# irs-takachi.net
KiCad netlist of a schematic drawn in EAGLE
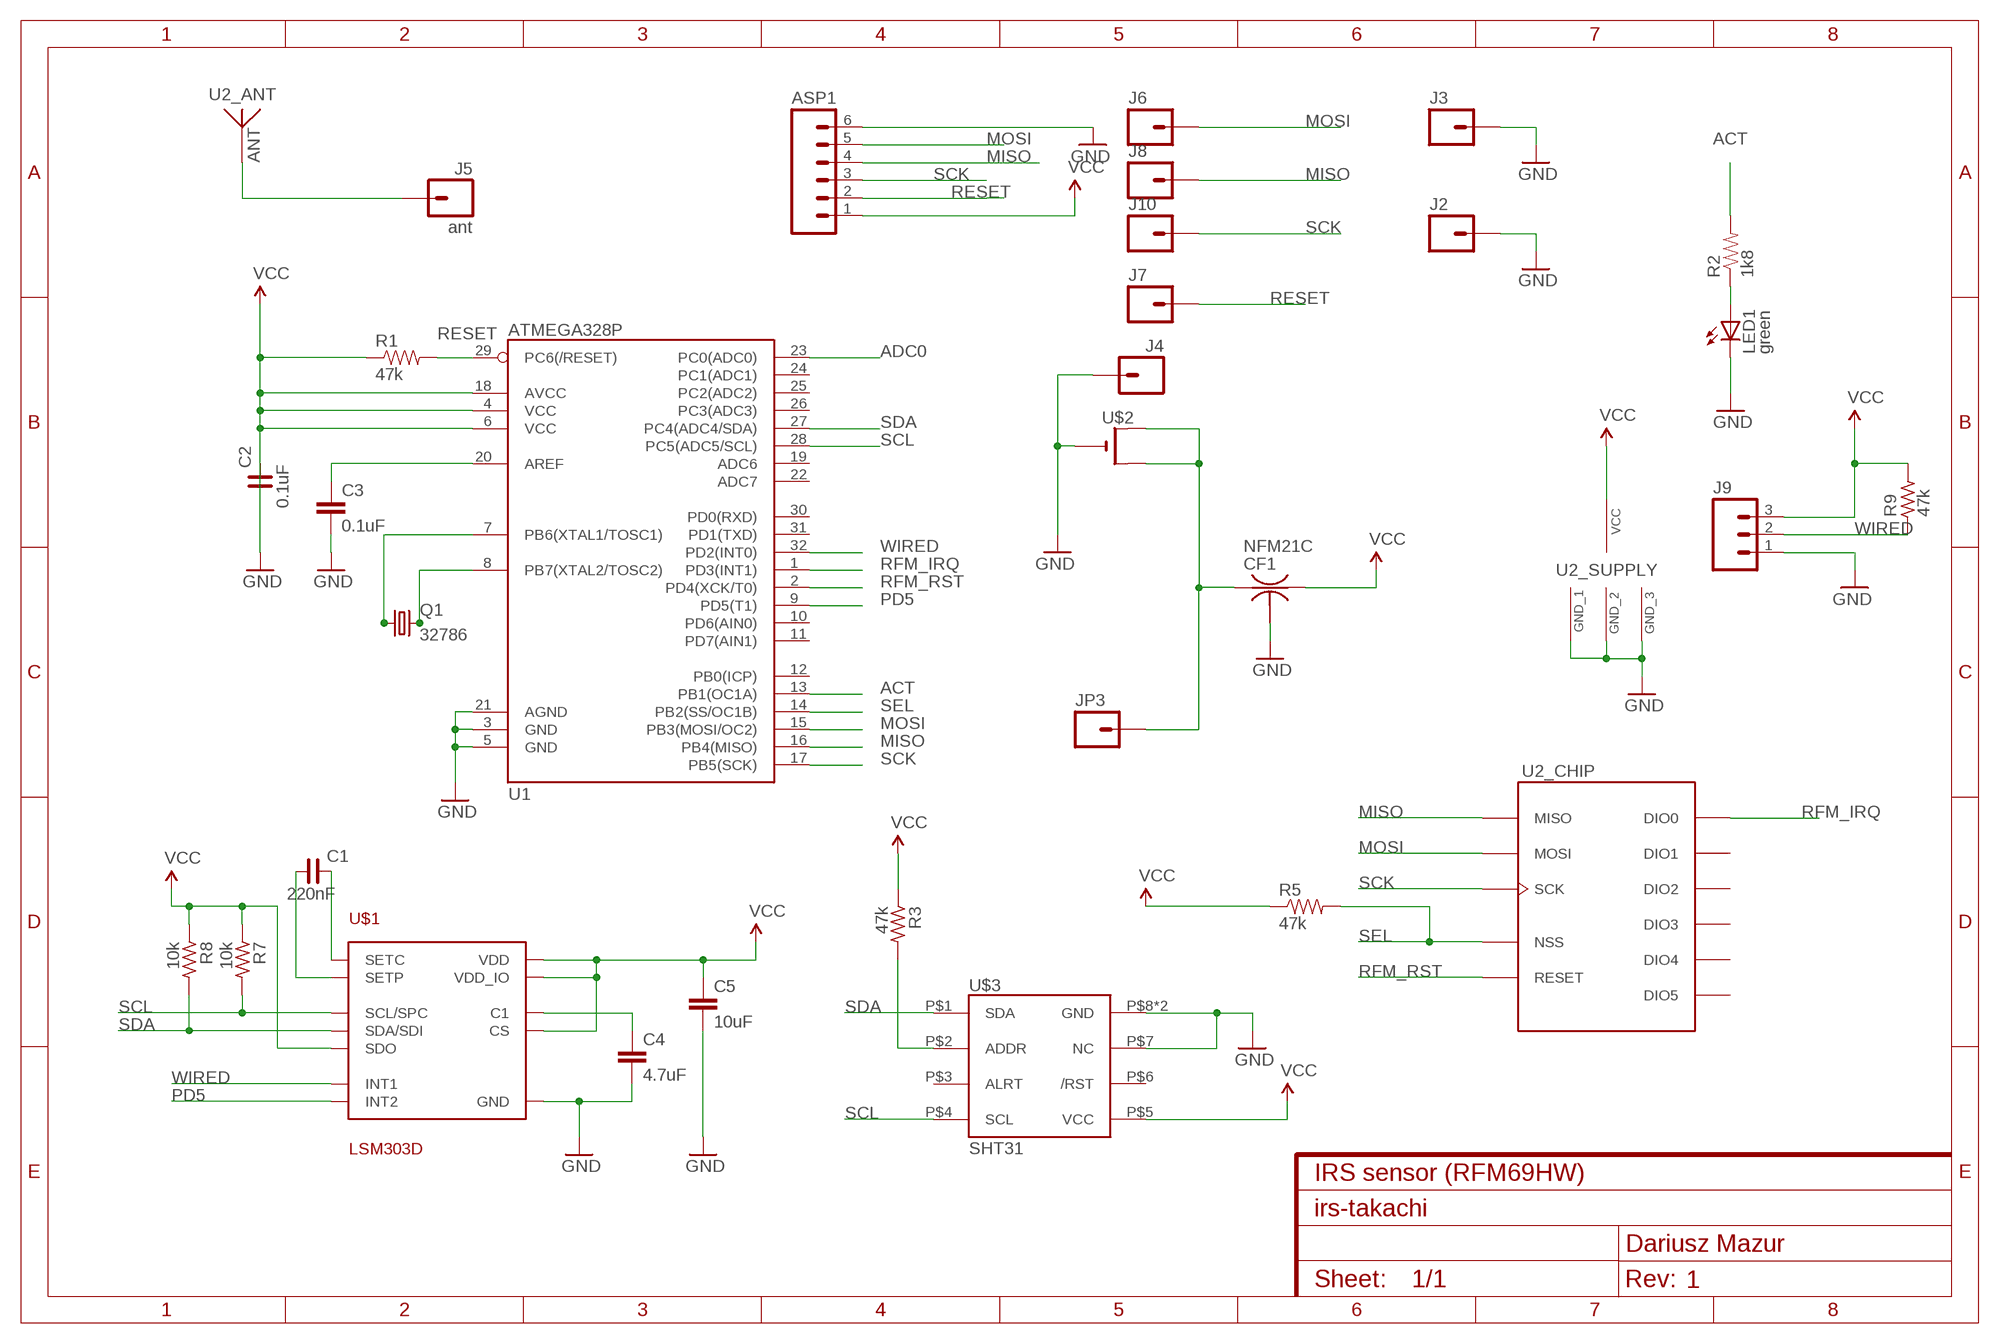
[diagram p0: schematic, sheet 1]

(export (version "E")
  (design (tool "Eeschema 10.0.6"))
  (components
    (comp (ref "ASP1")
      (value "M06NO_SILK_YES_STOP")
      (footprint "eagle-import:1X06_NO_SILK_YES_STOP")
      (libsource (lib "eagle-import") (part "M06NO_SILK_YES_STOP"))
    )
    (comp (ref "C1")
      (value "220nF")
      (footprint "eagle-import:C0603")
      (libsource (lib "eagle-import") (part "C_0603"))
    )
    (comp (ref "C2")
      (value "0.1uF")
      (footprint "eagle-import:C0603")
      (libsource (lib "eagle-import") (part "C_0603"))
    )
    (comp (ref "C3")
      (value "0.1uF")
      (footprint "eagle-import:0603-CAP")
      (libsource (lib "eagle-import") (part "0.1UF-25V(+80/-20%)(0603)"))
    )
    (comp (ref "C4")
      (value "4.7uF")
      (footprint "eagle-import:C0603K")
      (libsource (lib "eagle-import") (part "C-EUC0603K"))
    )
    (comp (ref "C5")
      (value "10uF")
      (footprint "eagle-import:0805-CAP")
      (libsource (lib "eagle-import") (part "10UF10V10%(0805)"))
    )
    (comp (ref "CF1")
      (value "NFM21C")
      (footprint "eagle-import:NFM21C")
      (fields (field (name "MPN") "NFM21CC102R1H3D"))
      (libsource (lib "eagle-import") (part "NFM21C"))
    )
    (comp (ref "J2")
      (value "M01PTH_NO_SILK_YES_STOP")
      (footprint "eagle-import:1X01_NO_SILK")
      (libsource (lib "eagle-import") (part "M01PTH_NO_SILK_YES_STOP"))
    )
    (comp (ref "J3")
      (value "M01PTH_NO_SILK_YES_STOP")
      (footprint "eagle-import:1X01_NO_SILK")
      (libsource (lib "eagle-import") (part "M01PTH_NO_SILK_YES_STOP"))
    )
    (comp (ref "J4")
      (value "M01SNAP-FEMALE")
      (footprint "eagle-import:SNAP-FEMALE")
      (libsource (lib "eagle-import") (part "M01SNAP-FEMALE"))
    )
    (comp (ref "J5")
      (value "ant")
      (footprint "eagle-import:1X01_NO_SILK")
      (libsource (lib "eagle-import") (part "M01PTH_NO_SILK_YES_STOP"))
    )
    (comp (ref "J6")
      (value "M01SMD-4.5X1.5")
      (footprint "eagle-import:PAD-1.5X4.5")
      (libsource (lib "eagle-import") (part "M01SMD-4.5X1.5"))
    )
    (comp (ref "J7")
      (value "M01SMD-4.5X1.5")
      (footprint "eagle-import:PAD-1.5X4.5")
      (libsource (lib "eagle-import") (part "M01SMD-4.5X1.5"))
    )
    (comp (ref "J8")
      (value "M01SMD-4.5X1.5")
      (footprint "eagle-import:PAD-1.5X4.5")
      (libsource (lib "eagle-import") (part "M01SMD-4.5X1.5"))
    )
    (comp (ref "J9")
      (value "M031X03_NO_SILK")
      (footprint "eagle-import:1X03_NO_SILK")
      (libsource (lib "eagle-import") (part "M031X03_NO_SILK"))
    )
    (comp (ref "J10")
      (value "M01SMD-4.5X1.5")
      (footprint "eagle-import:PAD-1.5X4.5")
      (libsource (lib "eagle-import") (part "M01SMD-4.5X1.5"))
    )
    (comp (ref "JP3")
      (value "M01SMDNS")
      (footprint "eagle-import:1X01NS")
      (libsource (lib "eagle-import") (part "M01SMDNS"))
    )
    (comp (ref "LED1")
      (value "green")
      (footprint "eagle-import:LED-0603")
      (libsource (lib "eagle-import") (part "LED0603"))
    )
    (comp (ref "Q1")
      (value "32786")
      (footprint "eagle-import:MC-306")
      (fields (field (name "MPN") "MC-306 60.0KHZ  100PPM ,12.5PF"))
      (libsource (lib "eagle-import") (part "MC-306"))
    )
    (comp (ref "R1")
      (value "47k")
      (footprint "eagle-import:0603-RES")
      (libsource (lib "eagle-import") (part "RESISTOR0603-RES"))
    )
    (comp (ref "R2")
      (value "1k8")
      (footprint "eagle-import:0603-RES")
      (libsource (lib "eagle-import") (part "RESISTOR0603-RES"))
    )
    (comp (ref "R3")
      (value "47k")
      (footprint "eagle-import:R0603")
      (libsource (lib "eagle-import") (part "R_0603"))
    )
    (comp (ref "R5")
      (value "47k")
      (footprint "eagle-import:0603-RES")
      (libsource (lib "eagle-import") (part "RESISTOR0603-RES"))
    )
    (comp (ref "R7")
      (value "10k")
      (footprint "eagle-import:R0603")
      (libsource (lib "eagle-import") (part "R_0603"))
    )
    (comp (ref "R8")
      (value "10k")
      (footprint "eagle-import:R0603")
      (libsource (lib "eagle-import") (part "R_0603"))
    )
    (comp (ref "R9")
      (value "47k")
      (footprint "eagle-import:R0603")
      (libsource (lib "eagle-import") (part "R_0603"))
    )
    (comp (ref "U$1")
      (value "LSM303D")
      (footprint "eagle-import:LGA16-3MM")
      (libsource (lib "eagle-import") (part "LSM303D"))
    )
    (comp (ref "U$2")
      (value "CR2032THM")
      (footprint "eagle-import:CR2032-THRU")
      (libsource (lib "eagle-import") (part "CR2032THM"))
    )
    (comp (ref "U$3")
      (value "SHT31")
      (footprint "eagle-import:SHT3X")
      (libsource (lib "eagle-import") (part "SHT31-DIS"))
    )
    (comp (ref "U1")
      (value "ATMEGA328P")
      (footprint "eagle-import:TQFP32-08")
      (libsource (lib "eagle-import") (part "ATMEGA328_SMT"))
    )
    (comp (ref "U2")
      (value "RFM69HCW-S2")
      (footprint "eagle-import:HOPE-RF-16")
      (libsource (lib "eagle-import") (part "RFM69HCW-S2"))
    )
  )
  (nets
    (net (code "1") (name "/ACT") (class "Default")
      (node (ref "R2") (pin "2") (pinfunction "2_2") (pintype "passive"))
      (node (ref "U1") (pin "13") (pinfunction "PB1(OC1A)_13") (pintype "bidirectional"))
    )
    (net (code "2") (name "/ADC0") (class "Default")
      (node (ref "U1") (pin "23") (pinfunction "PC0(ADC0)_23") (pintype "bidirectional"))
    )
    (net (code "3") (name "/MISO") (class "Default")
      (node (ref "ASP1") (pin "4") (pinfunction "4_4") (pintype "passive"))
      (node (ref "J8") (pin "P$1") (pinfunction "1_P$1") (pintype "passive"))
      (node (ref "U1") (pin "16") (pinfunction "PB4(MISO)_16") (pintype "bidirectional"))
      (node (ref "U2") (pin "MISO") (pinfunction "MISO_MISO") (pintype "input"))
    )
    (net (code "4") (name "/MOSI") (class "Default")
      (node (ref "ASP1") (pin "5") (pinfunction "5_5") (pintype "passive"))
      (node (ref "J6") (pin "P$1") (pinfunction "1_P$1") (pintype "passive"))
      (node (ref "U1") (pin "15") (pinfunction "PB3(MOSI/OC2)_15") (pintype "bidirectional"))
      (node (ref "U2") (pin "MOSI") (pinfunction "MOSI_MOSI") (pintype "output"))
    )
    (net (code "5") (name "/PD5") (class "Default")
      (node (ref "U$1") (pin "9") (pinfunction "INT2_9") (pintype "bidirectional"))
      (node (ref "U1") (pin "9") (pinfunction "PD5(T1)_9") (pintype "bidirectional"))
    )
    (net (code "6") (name "/RESET") (class "Default")
      (node (ref "ASP1") (pin "2") (pinfunction "2_2") (pintype "passive"))
      (node (ref "J7") (pin "P$1") (pinfunction "1_P$1") (pintype "passive"))
      (node (ref "R1") (pin "2") (pinfunction "2_2") (pintype "passive"))
      (node (ref "U1") (pin "29") (pinfunction "PC6(/RESET)_29") (pintype "bidirectional"))
    )
    (net (code "7") (name "/RFM_IRQ") (class "Default")
      (node (ref "U1") (pin "1") (pinfunction "PD3(INT1)_1") (pintype "bidirectional"))
      (node (ref "U2") (pin "DIO0") (pinfunction "DIO0_DIO0") (pintype "bidirectional"))
    )
    (net (code "8") (name "/RFM_RST") (class "Default")
      (node (ref "U1") (pin "2") (pinfunction "PD4(XCK/T0)_2") (pintype "bidirectional"))
      (node (ref "U2") (pin "RESET") (pinfunction "RESET_RESET") (pintype "bidirectional"))
    )
    (net (code "9") (name "/SCK") (class "Default")
      (node (ref "ASP1") (pin "3") (pinfunction "3_3") (pintype "passive"))
      (node (ref "J10") (pin "P$1") (pinfunction "1_P$1") (pintype "passive"))
      (node (ref "U1") (pin "17") (pinfunction "PB5(SCK)_17") (pintype "bidirectional"))
      (node (ref "U2") (pin "SCK") (pinfunction "SCK_SCK") (pintype "input"))
    )
    (net (code "10") (name "/SCL") (class "Default")
      (node (ref "R7") (pin "2") (pinfunction "2_2") (pintype "passive"))
      (node (ref "U$1") (pin "4") (pinfunction "SCL/SPC_4") (pintype "bidirectional"))
      (node (ref "U$3") (pin "P$4") (pinfunction "SCL_P$4") (pintype "bidirectional"))
      (node (ref "U1") (pin "28") (pinfunction "PC5(ADC5/SCL)_28") (pintype "bidirectional"))
    )
    (net (code "11") (name "/SDA") (class "Default")
      (node (ref "R8") (pin "2") (pinfunction "2_2") (pintype "passive"))
      (node (ref "U$1") (pin "6") (pinfunction "SDA/SDI_6") (pintype "bidirectional"))
      (node (ref "U$3") (pin "P$1") (pinfunction "SDA_P$1") (pintype "bidirectional"))
      (node (ref "U1") (pin "27") (pinfunction "PC4(ADC4/SDA)_27") (pintype "bidirectional"))
    )
    (net (code "12") (name "/SEL") (class "Default")
      (node (ref "R5") (pin "2") (pinfunction "2_2") (pintype "passive"))
      (node (ref "U1") (pin "14") (pinfunction "PB2(SS/OC1B)_14") (pintype "bidirectional"))
      (node (ref "U2") (pin "NSS") (pinfunction "NSS_NSS") (pintype "input"))
    )
    (net (code "13") (name "/WIRED") (class "Default")
      (node (ref "J9") (pin "2") (pinfunction "2_2") (pintype "passive"))
      (node (ref "R9") (pin "1") (pinfunction "1_1") (pintype "passive"))
      (node (ref "U$1") (pin "11") (pinfunction "INT1_11") (pintype "bidirectional"))
      (node (ref "U1") (pin "32") (pinfunction "PD2(INT0)_32") (pintype "bidirectional"))
    )
    (net (code "14") (name "GND") (class "Default")
      (node (ref "ASP1") (pin "6") (pinfunction "6_6") (pintype "passive"))
      (node (ref "C2") (pin "2") (pinfunction "2_2") (pintype "passive"))
      (node (ref "C3") (pin "2") (pinfunction "2_2") (pintype "passive"))
      (node (ref "C4") (pin "2") (pinfunction "2_2") (pintype "passive"))
      (node (ref "C5") (pin "2") (pinfunction "2_2") (pintype "passive"))
      (node (ref "CF1") (pin "2@1") (pinfunction "2_2@1") (pintype "passive"))
      (node (ref "J2") (pin "1") (pinfunction "1_1") (pintype "passive"))
      (node (ref "J3") (pin "1") (pinfunction "1_1") (pintype "passive"))
      (node (ref "J4") (pin "1") (pinfunction "1_1") (pintype "passive"))
      (node (ref "J9") (pin "1") (pinfunction "1_1") (pintype "passive"))
      (node (ref "LED1") (pin "C") (pinfunction "C_C") (pintype "passive"))
      (node (ref "U$1") (pin "10") (pinfunction "GND_10") (pintype "power_in"))
      (node (ref "U$1") (pin "12") (pinfunction "GND_12") (pintype "power_in"))
      (node (ref "U$1") (pin "13") (pinfunction "GND_13") (pintype "power_in"))
      (node (ref "U$1") (pin "16") (pinfunction "GND_16") (pintype "power_in"))
      (node (ref "U$1") (pin "5") (pinfunction "GND_5") (pintype "power_in"))
      (node (ref "U$2") (pin "-") (pinfunction "-_-") (pintype "passive"))
      (node (ref "U$3") (pin "P$7") (pinfunction "NC_P$7") (pintype "bidirectional"))
      (node (ref "U$3") (pin "P$8") (pinfunction "GND_P$8") (pintype "bidirectional"))
      (node (ref "U$3") (pin "PAD") (pinfunction "GND_PAD") (pintype "bidirectional"))
      (node (ref "U1") (pin "21") (pinfunction "AGND_21") (pintype "bidirectional"))
      (node (ref "U1") (pin "3") (pinfunction "GND_3") (pintype "bidirectional"))
      (node (ref "U1") (pin "5") (pinfunction "GND_5") (pintype "bidirectional"))
      (node (ref "U2") (pin "GND1") (pinfunction "GND_1_GND1") (pintype "power_in"))
      (node (ref "U2") (pin "GND2") (pinfunction "GND_2_GND2") (pintype "power_in"))
      (node (ref "U2") (pin "GND3") (pinfunction "GND_3_GND3") (pintype "power_in"))
    )
    (net (code "15") (name "Net-(J5-Pad1)") (class "Default")
      (node (ref "J5") (pin "1") (pinfunction "1_1") (pintype "passive"))
      (node (ref "U2") (pin "ANT") (pinfunction "ANT_ANT") (pintype "passive"))
    )
    (net (code "16") (name "Net-(LED1-PadA)") (class "Default")
      (node (ref "LED1") (pin "A") (pinfunction "A_A") (pintype "passive"))
      (node (ref "R2") (pin "1") (pinfunction "1_1") (pintype "passive"))
    )
    (net (code "17") (name "Net-(Q1-2)") (class "Default")
      (node (ref "Q1") (pin "4") (pinfunction "2_4") (pintype "passive"))
      (node (ref "U1") (pin "8") (pinfunction "PB7(XTAL2/TOSC2)_8") (pintype "bidirectional"))
    )
    (net (code "18") (name "Net-(U$1-C1)") (class "Default")
      (node (ref "C4") (pin "1") (pinfunction "1_1") (pintype "passive"))
      (node (ref "U$1") (pin "15") (pinfunction "C1_15") (pintype "bidirectional"))
    )
    (net (code "19") (name "Net-(U$1-SETC)") (class "Default")
      (node (ref "C1") (pin "2") (pinfunction "2_2") (pintype "passive"))
      (node (ref "U$1") (pin "2") (pinfunction "SETC_2") (pintype "bidirectional"))
    )
    (net (code "20") (name "Net-(U$1-SETP)") (class "Default")
      (node (ref "C1") (pin "1") (pinfunction "1_1") (pintype "passive"))
      (node (ref "U$1") (pin "3") (pinfunction "SETP_3") (pintype "bidirectional"))
    )
    (net (code "21") (name "Net-(U$2-+)") (class "Default")
      (node (ref "CF1") (pin "1") (pinfunction "1_1") (pintype "passive"))
      (node (ref "JP3") (pin "1") (pinfunction "1_1") (pintype "passive"))
      (node (ref "U$2") (pin "+1") (pinfunction "+_+1") (pintype "passive"))
      (node (ref "U$2") (pin "+2") (pinfunction "+1_+2") (pintype "passive"))
    )
    (net (code "22") (name "Net-(U$3-ADDR)") (class "Default")
      (node (ref "R3") (pin "2") (pinfunction "2_2") (pintype "passive"))
      (node (ref "U$3") (pin "P$2") (pinfunction "ADDR_P$2") (pintype "bidirectional"))
    )
    (net (code "23") (name "Net-(U1-AREF)") (class "Default")
      (node (ref "C3") (pin "1") (pinfunction "1_1") (pintype "passive"))
      (node (ref "U1") (pin "20") (pinfunction "AREF_20") (pintype "bidirectional"))
    )
    (net (code "24") (name "Net-(U1-PB6(XTAL1{slash}TOSC1))") (class "Default")
      (node (ref "Q1") (pin "1") (pinfunction "1_1") (pintype "passive"))
      (node (ref "U1") (pin "7") (pinfunction "PB6(XTAL1/TOSC1)_7") (pintype "bidirectional"))
    )
    (net (code "25") (name "VCC") (class "Default")
      (node (ref "ASP1") (pin "1") (pinfunction "1_1") (pintype "passive"))
      (node (ref "C2") (pin "1") (pinfunction "1_1") (pintype "passive"))
      (node (ref "C5") (pin "1") (pinfunction "1_1") (pintype "passive"))
      (node (ref "CF1") (pin "3") (pinfunction "3_3") (pintype "passive"))
      (node (ref "J9") (pin "3") (pinfunction "3_3") (pintype "passive"))
      (node (ref "R1") (pin "1") (pinfunction "1_1") (pintype "passive"))
      (node (ref "R3") (pin "1") (pinfunction "1_1") (pintype "passive"))
      (node (ref "R5") (pin "1") (pinfunction "1_1") (pintype "passive"))
      (node (ref "R7") (pin "1") (pinfunction "1_1") (pintype "passive"))
      (node (ref "R8") (pin "1") (pinfunction "1_1") (pintype "passive"))
      (node (ref "R9") (pin "2") (pinfunction "2_2") (pintype "passive"))
      (node (ref "U$1") (pin "1") (pinfunction "VDD_IO_1") (pintype "power_in"))
      (node (ref "U$1") (pin "14") (pinfunction "VDD_14") (pintype "bidirectional"))
      (node (ref "U$1") (pin "7") (pinfunction "SDO_7") (pintype "bidirectional"))
      (node (ref "U$1") (pin "8") (pinfunction "CS_8") (pintype "bidirectional"))
      (node (ref "U$3") (pin "P$5") (pinfunction "VCC_P$5") (pintype "bidirectional"))
      (node (ref "U1") (pin "18") (pinfunction "AVCC_18") (pintype "bidirectional"))
      (node (ref "U1") (pin "4") (pinfunction "VCC_4") (pintype "bidirectional"))
      (node (ref "U1") (pin "6") (pinfunction "VCC_6") (pintype "bidirectional"))
      (node (ref "U2") (pin "3.3V") (pinfunction "VCC_3.3V") (pintype "power_in"))
    )
    (net (code "26") (name "unconnected-(CF1-2-Pad2@2)") (class "Default")
      (node (ref "CF1") (pin "2@2") (pinfunction "2_2@2") (pintype "passive"))
    )
    (net (code "27") (name "unconnected-(U$3-ALRT-PadP$3)") (class "Default")
      (node (ref "U$3") (pin "P$3") (pinfunction "ALRT_P$3") (pintype "bidirectional"))
    )
    (net (code "28") (name "unconnected-(U$3-{slash}RST-PadP$6)") (class "Default")
      (node (ref "U$3") (pin "P$6") (pinfunction "/RST_P$6") (pintype "bidirectional"))
    )
    (net (code "29") (name "unconnected-(U1-ADC6-Pad19)") (class "Default")
      (node (ref "U1") (pin "19") (pinfunction "ADC6_19") (pintype "bidirectional"))
    )
    (net (code "30") (name "unconnected-(U1-ADC7-Pad22)") (class "Default")
      (node (ref "U1") (pin "22") (pinfunction "ADC7_22") (pintype "bidirectional"))
    )
    (net (code "31") (name "unconnected-(U1-PB0(ICP)-Pad12)") (class "Default")
      (node (ref "U1") (pin "12") (pinfunction "PB0(ICP)_12") (pintype "bidirectional"))
    )
    (net (code "32") (name "unconnected-(U1-PC1(ADC1)-Pad24)") (class "Default")
      (node (ref "U1") (pin "24") (pinfunction "PC1(ADC1)_24") (pintype "bidirectional"))
    )
    (net (code "33") (name "unconnected-(U1-PC2(ADC2)-Pad25)") (class "Default")
      (node (ref "U1") (pin "25") (pinfunction "PC2(ADC2)_25") (pintype "bidirectional"))
    )
    (net (code "34") (name "unconnected-(U1-PC3(ADC3)-Pad26)") (class "Default")
      (node (ref "U1") (pin "26") (pinfunction "PC3(ADC3)_26") (pintype "bidirectional"))
    )
    (net (code "35") (name "unconnected-(U1-PD0(RXD)-Pad30)") (class "Default")
      (node (ref "U1") (pin "30") (pinfunction "PD0(RXD)_30") (pintype "bidirectional"))
    )
    (net (code "36") (name "unconnected-(U1-PD1(TXD)-Pad31)") (class "Default")
      (node (ref "U1") (pin "31") (pinfunction "PD1(TXD)_31") (pintype "bidirectional"))
    )
    (net (code "37") (name "unconnected-(U1-PD6(AIN0)-Pad10)") (class "Default")
      (node (ref "U1") (pin "10") (pinfunction "PD6(AIN0)_10") (pintype "bidirectional"))
    )
    (net (code "38") (name "unconnected-(U1-PD7(AIN1)-Pad11)") (class "Default")
      (node (ref "U1") (pin "11") (pinfunction "PD7(AIN1)_11") (pintype "bidirectional"))
    )
    (net (code "39") (name "unconnected-(U2-PadDIO1)") (class "Default")
      (node (ref "U2") (pin "DIO1") (pinfunction "DIO1_DIO1") (pintype "bidirectional"))
    )
    (net (code "40") (name "unconnected-(U2-PadDIO2)") (class "Default")
      (node (ref "U2") (pin "DIO2") (pinfunction "DIO2_DIO2") (pintype "bidirectional"))
    )
    (net (code "41") (name "unconnected-(U2-PadDIO3)") (class "Default")
      (node (ref "U2") (pin "DIO3") (pinfunction "DIO3_DIO3") (pintype "bidirectional"))
    )
    (net (code "42") (name "unconnected-(U2-PadDIO4)") (class "Default")
      (node (ref "U2") (pin "DIO4") (pinfunction "DIO4_DIO4") (pintype "bidirectional"))
    )
    (net (code "43") (name "unconnected-(U2-PadDIO5)") (class "Default")
      (node (ref "U2") (pin "DIO5") (pinfunction "DIO5_DIO5") (pintype "bidirectional"))
    )
  )
)
